# Console.net
KiCad netlist of a schematic drawn in Altium Designer
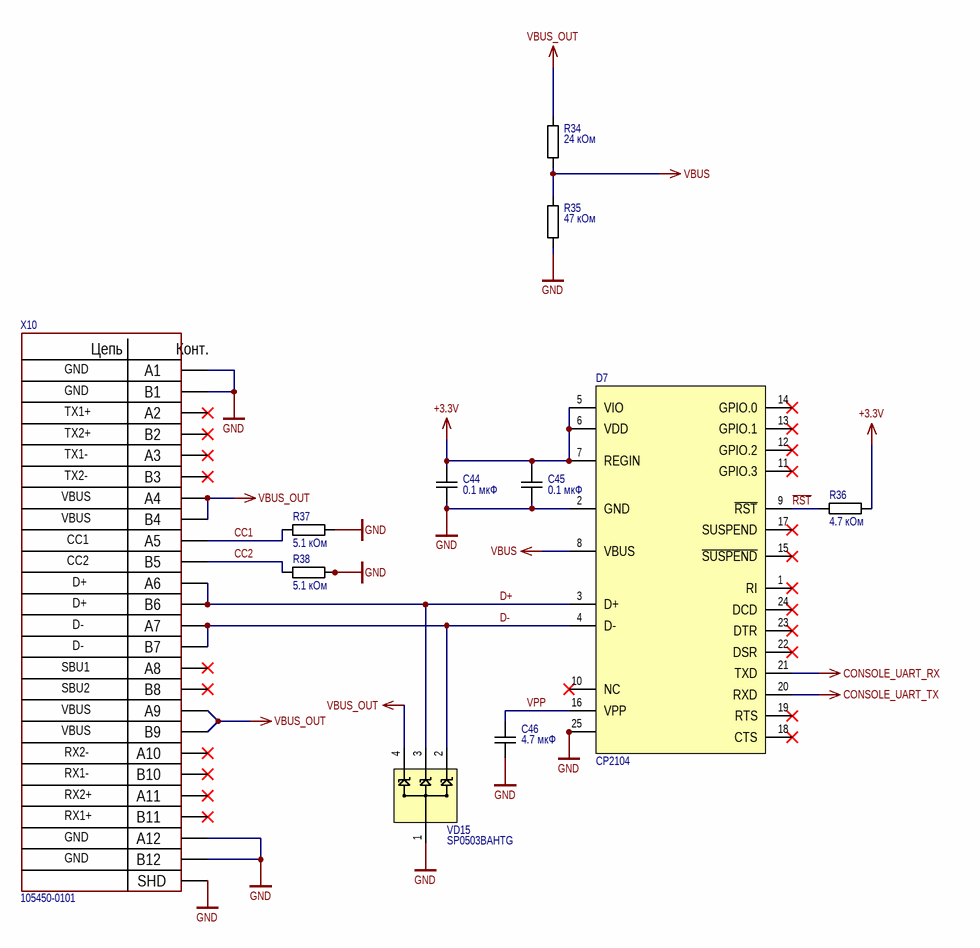
[diagram p0: Console.SchDoc]

(export (version "E")
  (design (tool "Eeschema 10.0.6"))
  (components
    (comp (ref "C44")
      (value "0.1 мкФ")
      (footprint "CAP-0603")
      (description "Конденсатор")
      (fields (field (name "TOLERANCE") "10%") (field (name "VOLTAGE") "16 В"))
      (libsource (lib "load") (part "Cap_0603"))
    )
    (comp (ref "C45")
      (value "0.1 мкФ")
      (footprint "CAP-0603")
      (description "Конденсатор")
      (fields (field (name "TOLERANCE") "10%") (field (name "VOLTAGE") "16 В"))
      (libsource (lib "load") (part "Cap_0603"))
    )
    (comp (ref "C46")
      (value "4.7 мкФ")
      (footprint "CAP-0603")
      (description "Конденсатор")
      (fields (field (name "TOLERANCE") "10%") (field (name "VOLTAGE") "35 В"))
      (libsource (lib "load") (part "Cap_0603"))
    )
    (comp (ref "D7")
      (value "CP2104")
      (footprint "QFN-24")
      (description "Interface IC full speed basic USB type-C controller USB 2.0 3.3V, CP2104-F03-GMR, WFQFN-24")
      (fields
        (field (name "MANUFACTURER") "Silicon Labs")
        (field (name "MANUFACTURER PART NUMBER") "CP2104-F03-GMR")
      )
      (libsource (lib "PiezoControlBoard") (part "CP2104-F03-GMR"))
    )
    (comp (ref "R34")
      (value "24 кОм")
      (footprint "RES-0603")
      (description "Резистор")
      (fields (field (name "POWER") "0.1 Вт") (field (name "TOLERANCE") "1%"))
      (libsource (lib "load") (part "Res_0603"))
    )
    (comp (ref "R35")
      (value "47 кОм")
      (footprint "RES-0603")
      (description "Резистор")
      (fields (field (name "POWER") "0.1 Вт") (field (name "TOLERANCE") "1%"))
      (libsource (lib "load") (part "Res_0603"))
    )
    (comp (ref "R36")
      (value "4.7 кОм")
      (footprint "RES-0603")
      (description "Резистор")
      (fields (field (name "POWER") "0.1 Вт") (field (name "TOLERANCE") "1%"))
      (libsource (lib "load") (part "Res_0603"))
    )
    (comp (ref "R37")
      (value "5.1 кОм")
      (footprint "RES-0603")
      (description "Резистор")
      (fields (field (name "POWER") "0.1 Вт") (field (name "TOLERANCE") "1%"))
      (libsource (lib "load") (part "Res_0603"))
    )
    (comp (ref "R38")
      (value "5.1 кОм")
      (footprint "RES-0603")
      (description "Резистор")
      (fields (field (name "POWER") "0.1 Вт") (field (name "TOLERANCE") "1%"))
      (libsource (lib "load") (part "Res_0603"))
    )
    (comp (ref "VD15")
      (value "SP0503BAHTG")
      (footprint "SOT-143")
      (description "SP050xBA Series 8.5 V 30 pF Triple Uni-Directional TVS Avalanche Diode-SOT143-4")
      (fields (field (name "MANUFACTURER") "Littelfuse"))
      (libsource (lib "PiezoControlBoard") (part "SP0503BAHTG"))
    )
    (comp (ref "X10")
      (value "105450-0101")
      (footprint "USB-C")
      (description "USB Connector, 24 Contact(s), Female, Right Angle, Surface Mount Terminal, Receptacle")
      (fields
        (field (name "MANUFACTURER") "Molex")
        (field (name "B12") "GND")
        (field (name "A12") "GND")
        (field (name "B11") "RX1+")
        (field (name "A11") "RX2+")
        (field (name "B10") "RX1-")
        (field (name "A10") "RX2-")
        (field (name "B9") "VBUS")
        (field (name "A9") "VBUS")
        (field (name "B8") "SBU2")
        (field (name "A8") "SBU1")
        (field (name "B7") "D-")
        (field (name "A7") "D-")
        (field (name "B6") "D+")
        (field (name "A6") "D+")
        (field (name "B5") "CC2")
        (field (name "A5") "CC1")
        (field (name "B4") "VBUS")
        (field (name "A4") "VBUS")
        (field (name "B3") "TX2-")
        (field (name "A3") "TX1-")
        (field (name "B2") "TX2+")
        (field (name "A2") "TX1+")
        (field (name "B1") "GND")
        (field (name "A1") "GND")
      )
      (libsource (lib "PiezoControlBoard") (part "105450-0101"))
    )
  )
  (nets
    (net (code "1") (name "+3.3V") (class "Default")
      (node (ref "C44") (pin "2") (pinfunction "2_2") (pintype "passive"))
      (node (ref "C45") (pin "2") (pinfunction "2_2") (pintype "passive"))
      (node (ref "D7") (pin "5") (pinfunction "VIO_5") (pintype "passive"))
      (node (ref "D7") (pin "6") (pinfunction "VDD_6") (pintype "passive"))
      (node (ref "D7") (pin "7") (pinfunction "REGIN_7") (pintype "passive"))
      (node (ref "R36") (pin "1") (pinfunction "1_1") (pintype "passive"))
    )
    (net (code "2") (name "/CC1") (class "Default")
      (node (ref "R37") (pin "2") (pinfunction "2_2") (pintype "passive"))
      (node (ref "X10") (pin "A5") (pinfunction "A5_A5") (pintype "passive"))
    )
    (net (code "3") (name "/CC2") (class "Default")
      (node (ref "R38") (pin "2") (pinfunction "2_2") (pintype "passive"))
      (node (ref "X10") (pin "B5") (pinfunction "B5_B5") (pintype "passive"))
    )
    (net (code "4") (name "/D+") (class "Default")
      (node (ref "D7") (pin "3") (pinfunction "D+_3") (pintype "passive"))
      (node (ref "VD15") (pin "3") (pinfunction "3_3") (pintype "passive"))
      (node (ref "X10") (pin "A6") (pinfunction "A6_A6") (pintype "passive"))
      (node (ref "X10") (pin "B6") (pinfunction "B6_B6") (pintype "passive"))
    )
    (net (code "5") (name "/D-") (class "Default")
      (node (ref "D7") (pin "4") (pinfunction "D-_4") (pintype "passive"))
      (node (ref "VD15") (pin "2") (pinfunction "2_2") (pintype "passive"))
      (node (ref "X10") (pin "A7") (pinfunction "A7_A7") (pintype "passive"))
      (node (ref "X10") (pin "B7") (pinfunction "B7_B7") (pintype "passive"))
    )
    (net (code "6") (name "/VPP") (class "Default")
      (node (ref "C46") (pin "2") (pinfunction "2_2") (pintype "passive"))
      (node (ref "D7") (pin "16") (pinfunction "VPP_16") (pintype "passive"))
    )
    (net (code "7") (name "/~{RST}") (class "Default")
      (node (ref "D7") (pin "9") (pinfunction "~{RST}_9") (pintype "passive"))
      (node (ref "R36") (pin "2") (pinfunction "2_2") (pintype "passive"))
    )
    (net (code "8") (name "CONSOLE_UART_RX") (class "Default")
      (node (ref "D7") (pin "21") (pinfunction "TXD_21") (pintype "passive"))
    )
    (net (code "9") (name "CONSOLE_UART_TX") (class "Default")
      (node (ref "D7") (pin "20") (pinfunction "RXD_20") (pintype "passive"))
    )
    (net (code "10") (name "GND") (class "Default")
      (node (ref "C44") (pin "1") (pinfunction "1_1") (pintype "passive"))
      (node (ref "C45") (pin "1") (pinfunction "1_1") (pintype "passive"))
      (node (ref "C46") (pin "1") (pinfunction "1_1") (pintype "passive"))
      (node (ref "D7") (pin "2") (pinfunction "GND_2") (pintype "passive"))
      (node (ref "D7") (pin "25") (pintype "passive"))
      (node (ref "R35") (pin "2") (pinfunction "2_2") (pintype "passive"))
      (node (ref "R37") (pin "1") (pinfunction "1_1") (pintype "passive"))
      (node (ref "R38") (pin "1") (pinfunction "1_1") (pintype "passive"))
      (node (ref "VD15") (pin "1") (pinfunction "1_1") (pintype "passive"))
      (node (ref "X10") (pin "A1") (pinfunction "A1_A1") (pintype "passive"))
      (node (ref "X10") (pin "A12") (pinfunction "A12_A12") (pintype "passive"))
      (node (ref "X10") (pin "B1") (pinfunction "B1_B1") (pintype "passive"))
      (node (ref "X10") (pin "B12") (pinfunction "B12_B12") (pintype "passive"))
      (node (ref "X10") (pin "SHD") (pinfunction "SHD_SHD") (pintype "passive"))
    )
    (net (code "11") (name "VBUS") (class "Default")
      (node (ref "D7") (pin "8") (pinfunction "VBUS_8") (pintype "passive"))
      (node (ref "R34") (pin "2") (pinfunction "2_2") (pintype "passive"))
      (node (ref "R35") (pin "1") (pinfunction "1_1") (pintype "passive"))
    )
    (net (code "12") (name "VBUS_OUT") (class "Default")
      (node (ref "R34") (pin "1") (pinfunction "1_1") (pintype "passive"))
      (node (ref "VD15") (pin "4") (pinfunction "4_4") (pintype "passive"))
      (node (ref "X10") (pin "A4") (pinfunction "A4_A4") (pintype "passive"))
      (node (ref "X10") (pin "A9") (pinfunction "A9_A9") (pintype "passive"))
      (node (ref "X10") (pin "B4") (pinfunction "B4_B4") (pintype "passive"))
      (node (ref "X10") (pin "B9") (pinfunction "B9_B9") (pintype "passive"))
    )
    (net (code "13") (name "unconnected-(D7-CTS-Pad18)") (class "Default")
      (node (ref "D7") (pin "18") (pinfunction "CTS_18") (pintype "passive+no_connect"))
    )
    (net (code "14") (name "unconnected-(D7-DCD-Pad24)") (class "Default")
      (node (ref "D7") (pin "24") (pinfunction "DCD_24") (pintype "passive+no_connect"))
    )
    (net (code "15") (name "unconnected-(D7-DSR-Pad22)") (class "Default")
      (node (ref "D7") (pin "22") (pinfunction "DSR_22") (pintype "passive+no_connect"))
    )
    (net (code "16") (name "unconnected-(D7-DTR-Pad23)") (class "Default")
      (node (ref "D7") (pin "23") (pinfunction "DTR_23") (pintype "passive+no_connect"))
    )
    (net (code "17") (name "unconnected-(D7-GPIO.0-Pad14)") (class "Default")
      (node (ref "D7") (pin "14") (pinfunction "GPIO.0_14") (pintype "passive+no_connect"))
    )
    (net (code "18") (name "unconnected-(D7-GPIO.1-Pad13)") (class "Default")
      (node (ref "D7") (pin "13") (pinfunction "GPIO.1_13") (pintype "passive+no_connect"))
    )
    (net (code "19") (name "unconnected-(D7-GPIO.2-Pad12)") (class "Default")
      (node (ref "D7") (pin "12") (pinfunction "GPIO.2_12") (pintype "passive+no_connect"))
    )
    (net (code "20") (name "unconnected-(D7-GPIO.3-Pad11)") (class "Default")
      (node (ref "D7") (pin "11") (pinfunction "GPIO.3_11") (pintype "passive+no_connect"))
    )
    (net (code "21") (name "unconnected-(D7-NC-Pad10)") (class "Default")
      (node (ref "D7") (pin "10") (pinfunction "NC_10") (pintype "passive+no_connect"))
    )
    (net (code "22") (name "unconnected-(D7-RI-Pad1)") (class "Default")
      (node (ref "D7") (pin "1") (pinfunction "RI_1") (pintype "passive+no_connect"))
    )
    (net (code "23") (name "unconnected-(D7-RTS-Pad19)") (class "Default")
      (node (ref "D7") (pin "19") (pinfunction "RTS_19") (pintype "passive+no_connect"))
    )
    (net (code "24") (name "unconnected-(D7-SUSPEND-Pad17)") (class "Default")
      (node (ref "D7") (pin "17") (pinfunction "SUSPEND_17") (pintype "passive+no_connect"))
    )
    (net (code "25") (name "unconnected-(D7-~{SUSPEND}-Pad15)") (class "Default")
      (node (ref "D7") (pin "15") (pinfunction "~{SUSPEND}_15") (pintype "passive+no_connect"))
    )
    (net (code "26") (name "unconnected-(X10-B2-Pad2)") (class "Default")
      (node (ref "X10") (pin "2") (pinfunction "B2_2") (pintype "passive+no_connect"))
    )
    (net (code "27") (name "unconnected-(X10-PadA2)") (class "Default")
      (node (ref "X10") (pin "A2") (pinfunction "A2_A2") (pintype "passive+no_connect"))
    )
    (net (code "28") (name "unconnected-(X10-PadA3)") (class "Default")
      (node (ref "X10") (pin "A3") (pinfunction "A3_A3") (pintype "passive+no_connect"))
    )
    (net (code "29") (name "unconnected-(X10-PadA8)") (class "Default")
      (node (ref "X10") (pin "A8") (pinfunction "A8_A8") (pintype "passive+no_connect"))
    )
    (net (code "30") (name "unconnected-(X10-PadA10)") (class "Default")
      (node (ref "X10") (pin "A10") (pinfunction "A10_A10") (pintype "passive+no_connect"))
    )
    (net (code "31") (name "unconnected-(X10-PadA11)") (class "Default")
      (node (ref "X10") (pin "A11") (pinfunction "A11_A11") (pintype "passive+no_connect"))
    )
    (net (code "32") (name "unconnected-(X10-PadB3)") (class "Default")
      (node (ref "X10") (pin "B3") (pinfunction "B3_B3") (pintype "passive+no_connect"))
    )
    (net (code "33") (name "unconnected-(X10-PadB8)") (class "Default")
      (node (ref "X10") (pin "B8") (pinfunction "B8_B8") (pintype "passive+no_connect"))
    )
    (net (code "34") (name "unconnected-(X10-PadB10)") (class "Default")
      (node (ref "X10") (pin "B10") (pinfunction "B10_B10") (pintype "passive+no_connect"))
    )
    (net (code "35") (name "unconnected-(X10-PadB11)") (class "Default")
      (node (ref "X10") (pin "B11") (pinfunction "B11_B11") (pintype "passive+no_connect"))
    )
  )
)
